# lighthouse-v01.net
KiCad netlist of a schematic drawn in EAGLE
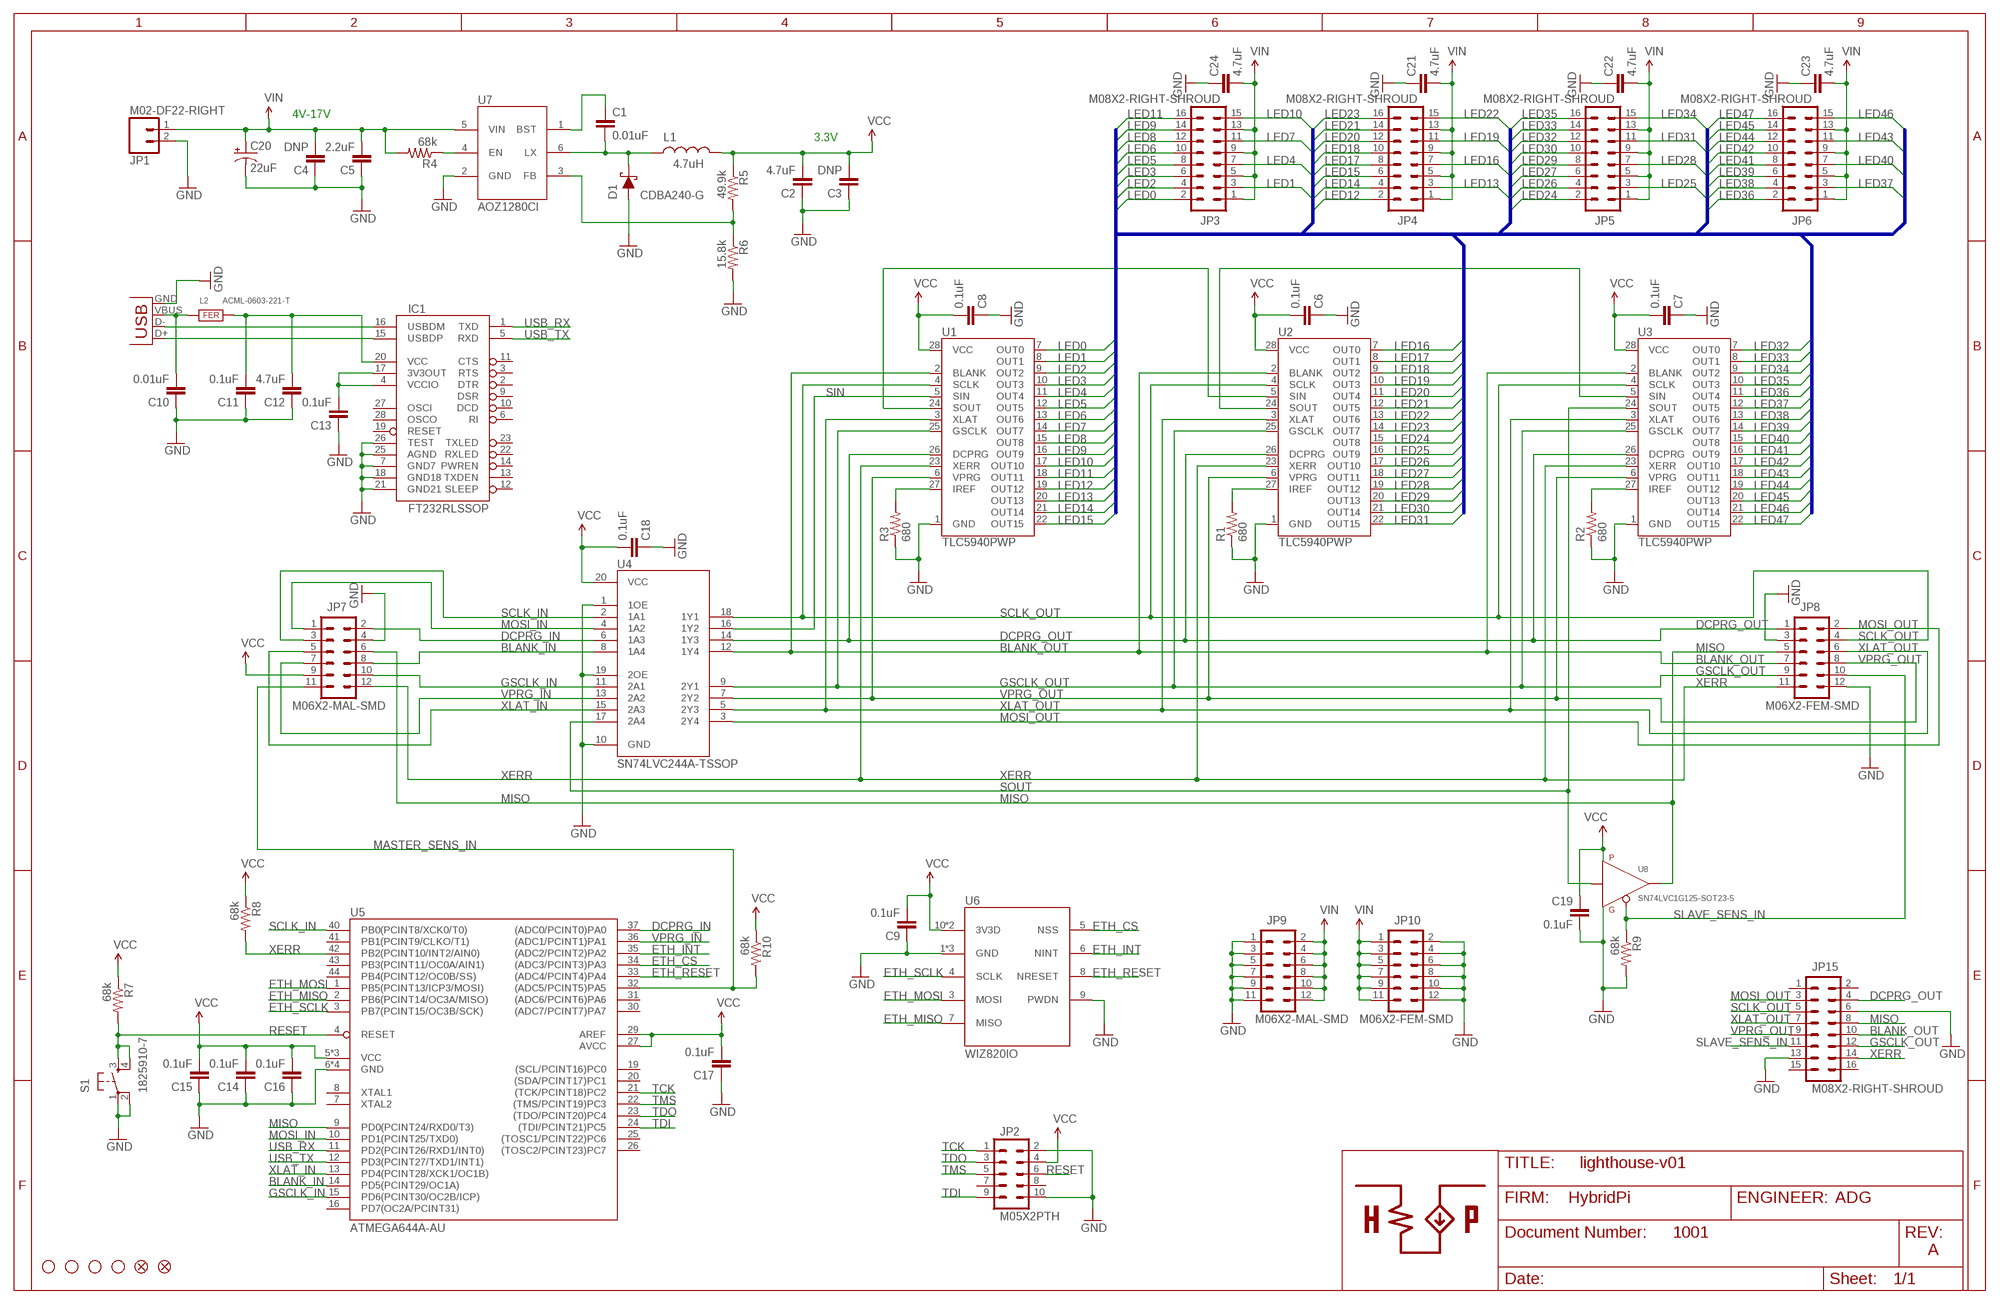
[diagram p0: schematic, sheet 1]

(export (version "E")
  (design (tool "Eeschema 10.0.6"))
  (components
    (comp (ref "C1")
      (value "0.01uF")
      (footprint "eagle-import:0603-CAP")
      (libsource (lib "eagle-import") (part "CAP0603-CAP"))
    )
    (comp (ref "C2")
      (value "4.7uF")
      (footprint "eagle-import:0805")
      (libsource (lib "eagle-import") (part "CAP0805"))
    )
    (comp (ref "C3")
      (value "DNP")
      (footprint "eagle-import:0805")
      (libsource (lib "eagle-import") (part "CAP0805"))
    )
    (comp (ref "C4")
      (value "DNP")
      (footprint "eagle-import:0805")
      (libsource (lib "eagle-import") (part "CAP0805"))
    )
    (comp (ref "C5")
      (value "2.2uF")
      (footprint "eagle-import:0805")
      (libsource (lib "eagle-import") (part "CAP0805"))
    )
    (comp (ref "C6")
      (value "0.1uF")
      (footprint "eagle-import:0603-CAP")
      (libsource (lib "eagle-import") (part "CAP0603-CAP"))
    )
    (comp (ref "C7")
      (value "0.1uF")
      (footprint "eagle-import:0603-CAP")
      (libsource (lib "eagle-import") (part "CAP0603-CAP"))
    )
    (comp (ref "C8")
      (value "0.1uF")
      (footprint "eagle-import:0603-CAP")
      (libsource (lib "eagle-import") (part "CAP0603-CAP"))
    )
    (comp (ref "C9")
      (value "0.1uF")
      (footprint "eagle-import:0603-CAP")
      (libsource (lib "eagle-import") (part "CAP0603-CAP"))
    )
    (comp (ref "C10")
      (value "0.01uF")
      (footprint "eagle-import:0603-CAP")
      (libsource (lib "eagle-import") (part "CAP0603-CAP"))
    )
    (comp (ref "C11")
      (value "0.1uF")
      (footprint "eagle-import:0603-CAP")
      (libsource (lib "eagle-import") (part "CAP0603-CAP"))
    )
    (comp (ref "C12")
      (value "4.7uF")
      (footprint "eagle-import:0805")
      (libsource (lib "eagle-import") (part "SparkFun-Passives_CAP0805"))
    )
    (comp (ref "C13")
      (value "0.1uF")
      (footprint "eagle-import:0603-CAP")
      (libsource (lib "eagle-import") (part "CAP0603-CAP"))
    )
    (comp (ref "C14")
      (value "0.1uF")
      (footprint "eagle-import:0603-CAP")
      (libsource (lib "eagle-import") (part "CAP0603-CAP"))
    )
    (comp (ref "C15")
      (value "0.1uF")
      (footprint "eagle-import:0603-CAP")
      (libsource (lib "eagle-import") (part "CAP0603-CAP"))
    )
    (comp (ref "C16")
      (value "0.1uF")
      (footprint "eagle-import:0603-CAP")
      (libsource (lib "eagle-import") (part "CAP0603-CAP"))
    )
    (comp (ref "C17")
      (value "0.1uF")
      (footprint "eagle-import:0603-CAP")
      (libsource (lib "eagle-import") (part "CAP0603-CAP"))
    )
    (comp (ref "C18")
      (value "0.1uF")
      (footprint "eagle-import:0603-CAP")
      (libsource (lib "eagle-import") (part "CAP0603-CAP"))
    )
    (comp (ref "C19")
      (value "0.1uF")
      (footprint "eagle-import:0603-CAP")
      (libsource (lib "eagle-import") (part "CAP0603-CAP"))
    )
    (comp (ref "C20")
      (value "22uF")
      (footprint "eagle-import:NIPPON_F80")
      (libsource (lib "eagle-import") (part "CAP_POLF80"))
    )
    (comp (ref "C21")
      (value "4.7uF")
      (footprint "eagle-import:1206")
      (libsource (lib "eagle-import") (part "SparkFun-Passives_CAP1206"))
    )
    (comp (ref "C22")
      (value "4.7uF")
      (footprint "eagle-import:1206")
      (libsource (lib "eagle-import") (part "SparkFun-Passives_CAP1206"))
    )
    (comp (ref "C23")
      (value "4.7uF")
      (footprint "eagle-import:1206")
      (libsource (lib "eagle-import") (part "SparkFun-Passives_CAP1206"))
    )
    (comp (ref "C24")
      (value "4.7uF")
      (footprint "eagle-import:1206")
      (libsource (lib "eagle-import") (part "SparkFun-Passives_CAP1206"))
    )
    (comp (ref "D1")
      (value "CDBA240-G")
      (footprint "eagle-import:DIODE-SMA")
      (libsource (lib "eagle-import") (part "DIODE-SCHOTTKY-SMA"))
    )
    (comp (ref "IC1")
      (value "FT232RLSSOP")
      (footprint "eagle-import:SSOP28DB")
      (libsource (lib "eagle-import") (part "FT232RLSSOP"))
    )
    (comp (ref "JP1")
      (value "M02-DF22-RIGHT")
      (footprint "eagle-import:M02-DF22-RIGHT")
      (libsource (lib "eagle-import") (part "M02-DF22-RIGHT"))
    )
    (comp (ref "JP2")
      (value "M05X2PTH")
      (footprint "eagle-import:AVR_ICSP")
      (libsource (lib "eagle-import") (part "M05X2PTH"))
    )
    (comp (ref "JP3")
      (value "M08X2-RIGHT-SHROUD")
      (footprint "eagle-import:2X8-RIGHT-SHROUD")
      (libsource (lib "eagle-import") (part "M08X2-RIGHT-SHROUD"))
    )
    (comp (ref "JP4")
      (value "M08X2-RIGHT-SHROUD")
      (footprint "eagle-import:2X8-RIGHT-SHROUD")
      (libsource (lib "eagle-import") (part "M08X2-RIGHT-SHROUD"))
    )
    (comp (ref "JP5")
      (value "M08X2-RIGHT-SHROUD")
      (footprint "eagle-import:2X8-RIGHT-SHROUD")
      (libsource (lib "eagle-import") (part "M08X2-RIGHT-SHROUD"))
    )
    (comp (ref "JP6")
      (value "M08X2-RIGHT-SHROUD")
      (footprint "eagle-import:2X8-RIGHT-SHROUD")
      (libsource (lib "eagle-import") (part "M08X2-RIGHT-SHROUD"))
    )
    (comp (ref "JP7")
      (value "M06X2-MAL-SMD")
      (footprint "eagle-import:2X6-SMD")
      (fields (field (name "EAGLEUP") "M06X2-MAL-SMD"))
      (libsource (lib "eagle-import") (part "M06X2-MAL-SMD"))
    )
    (comp (ref "JP8")
      (value "M06X2-FEM-SMD")
      (footprint "eagle-import:2X6-SMD")
      (libsource (lib "eagle-import") (part "M06X2-FEM-SMD"))
    )
    (comp (ref "JP9")
      (value "M06X2-MAL-SMD")
      (footprint "eagle-import:2X6-SMD")
      (fields (field (name "EAGLEUP") "M06X2-MAL-SMD"))
      (libsource (lib "eagle-import") (part "M06X2-MAL-SMD"))
    )
    (comp (ref "JP10")
      (value "M06X2-FEM-SMD")
      (footprint "eagle-import:2X6-SMD")
      (libsource (lib "eagle-import") (part "M06X2-FEM-SMD"))
    )
    (comp (ref "JP11")
      (value "STAND-OFF")
      (footprint "eagle-import:STAND-OFF")
      (libsource (lib "eagle-import") (part "STAND-OFF"))
    )
    (comp (ref "JP12")
      (value "STAND-OFF")
      (footprint "eagle-import:STAND-OFF")
      (libsource (lib "eagle-import") (part "STAND-OFF"))
    )
    (comp (ref "JP13")
      (value "STAND-OFF")
      (footprint "eagle-import:STAND-OFF")
      (libsource (lib "eagle-import") (part "STAND-OFF"))
    )
    (comp (ref "JP14")
      (value "STAND-OFF")
      (footprint "eagle-import:STAND-OFF")
      (libsource (lib "eagle-import") (part "STAND-OFF"))
    )
    (comp (ref "JP15")
      (value "M08X2-RIGHT-SHROUD")
      (footprint "eagle-import:2X8-RIGHT-SHROUD")
      (libsource (lib "eagle-import") (part "M08X2-RIGHT-SHROUD"))
    )
    (comp (ref "JP16")
      (value "FIDUCIAL1.5X3")
      (footprint "eagle-import:FIDUCIAL-1.5X3")
      (libsource (lib "eagle-import") (part "FIDUCIAL1.5X3"))
    )
    (comp (ref "JP17")
      (value "FIDUCIAL1.5X3")
      (footprint "eagle-import:FIDUCIAL-1.5X3")
      (libsource (lib "eagle-import") (part "FIDUCIAL1.5X3"))
    )
    (comp (ref "L1")
      (value "4.7uH")
      (footprint "eagle-import:SRN6045")
      (libsource (lib "eagle-import") (part "INDUCTOR-SRN6045"))
    )
    (comp (ref "L2")
      (value "ACML-0603-221-T")
      (footprint "eagle-import:0603")
      (libsource (lib "eagle-import") (part "FERRITE-BEAD-0603"))
    )
    (comp (ref "R1")
      (value "680")
      (footprint "eagle-import:0603-RES")
      (libsource (lib "eagle-import") (part "RESISTOR0603-RES"))
    )
    (comp (ref "R2")
      (value "680")
      (footprint "eagle-import:0603-RES")
      (libsource (lib "eagle-import") (part "RESISTOR0603-RES"))
    )
    (comp (ref "R3")
      (value "680")
      (footprint "eagle-import:0603-RES")
      (libsource (lib "eagle-import") (part "RESISTOR0603-RES"))
    )
    (comp (ref "R4")
      (value "68k")
      (footprint "eagle-import:0603-RES")
      (libsource (lib "eagle-import") (part "RESISTOR0603-RES"))
    )
    (comp (ref "R5")
      (value "49.9k")
      (footprint "eagle-import:0603-RES")
      (libsource (lib "eagle-import") (part "RESISTOR0603-RES"))
    )
    (comp (ref "R6")
      (value "15.8k")
      (footprint "eagle-import:0603-RES")
      (libsource (lib "eagle-import") (part "RESISTOR0603-RES"))
    )
    (comp (ref "R7")
      (value "68k")
      (footprint "eagle-import:0603-RES")
      (libsource (lib "eagle-import") (part "RESISTOR0603-RES"))
    )
    (comp (ref "R8")
      (value "68k")
      (footprint "eagle-import:0603-RES")
      (libsource (lib "eagle-import") (part "RESISTOR0603-RES"))
    )
    (comp (ref "R9")
      (value "68k")
      (footprint "eagle-import:0603-RES")
      (libsource (lib "eagle-import") (part "RESISTOR0603-RES"))
    )
    (comp (ref "R10")
      (value "68k")
      (footprint "eagle-import:0603-RES")
      (libsource (lib "eagle-import") (part "RESISTOR0603-RES"))
    )
    (comp (ref "S1")
      (value "1825910-7")
      (footprint "eagle-import:TACTILE-PTH")
      (libsource (lib "eagle-import") (part "TAC_SWITCHPTH"))
    )
    (comp (ref "U1")
      (value "TLC5940PWP")
      (footprint "eagle-import:TSSOP28-GROUNDPAD")
      (libsource (lib "eagle-import") (part "TLC5940PWP"))
    )
    (comp (ref "U2")
      (value "TLC5940PWP")
      (footprint "eagle-import:TSSOP28-GROUNDPAD")
      (libsource (lib "eagle-import") (part "TLC5940PWP"))
    )
    (comp (ref "U3")
      (value "TLC5940PWP")
      (footprint "eagle-import:TSSOP28-GROUNDPAD")
      (libsource (lib "eagle-import") (part "TLC5940PWP"))
    )
    (comp (ref "U4")
      (value "SN74LVC244A-TSSOP")
      (footprint "eagle-import:TSSOP-20")
      (libsource (lib "eagle-import") (part "SN74LVC244A-TSSOP"))
    )
    (comp (ref "U5")
      (value "ATMEGA644A-AU")
      (footprint "eagle-import:TQFP-44")
      (libsource (lib "eagle-import") (part "ATMEGA644A-AU"))
    )
    (comp (ref "U6")
      (value "WIZ820IO")
      (footprint "eagle-import:WIZ820IO")
      (libsource (lib "eagle-import") (part "WIZ820IO"))
    )
    (comp (ref "U7")
      (value "AOZ1280CI")
      (footprint "eagle-import:SOT23-6")
      (libsource (lib "eagle-import") (part "AOZ1280CI"))
    )
    (comp (ref "U8")
      (value "SN74LVC1G125-SOT23-5")
      (footprint "eagle-import:SOT23-5")
      (libsource (lib "eagle-import") (part "SN74LVC1G125-SOT23-5"))
    )
    (comp (ref "X1")
      (value "USBSMD")
      (footprint "eagle-import:USB-MINIB")
      (libsource (lib "eagle-import") (part "USBSMD"))
    )
  )
  (nets
    (net (code "1") (name "/BLANK_IN") (class "Default")
      (node (ref "JP7") (pin "8") (pinfunction "8_8") (pintype "passive"))
      (node (ref "U4") (pin "8") (pinfunction "1A4_8") (pintype "bidirectional"))
      (node (ref "U5") (pin "14") (pinfunction "PD5(PCINT29/OC1A)_14") (pintype "bidirectional"))
    )
    (net (code "2") (name "/BLANK_OUT") (class "Default")
      (node (ref "JP15") (pin "10") (pinfunction "10_10") (pintype "passive"))
      (node (ref "JP8") (pin "7") (pinfunction "7_7") (pintype "passive"))
      (node (ref "U1") (pin "2") (pinfunction "BLANK_2") (pintype "bidirectional"))
      (node (ref "U2") (pin "2") (pinfunction "BLANK_2") (pintype "bidirectional"))
      (node (ref "U3") (pin "2") (pinfunction "BLANK_2") (pintype "bidirectional"))
      (node (ref "U4") (pin "12") (pinfunction "1Y4_12") (pintype "bidirectional"))
    )
    (net (code "3") (name "/DCPRG_IN") (class "Default")
      (node (ref "JP7") (pin "2") (pinfunction "2_2") (pintype "passive"))
      (node (ref "U4") (pin "6") (pinfunction "1A3_6") (pintype "bidirectional"))
      (node (ref "U5") (pin "37") (pinfunction "(ADC0/PCINT0)PA0_37") (pintype "bidirectional"))
    )
    (net (code "4") (name "/DCPRG_OUT") (class "Default")
      (node (ref "JP15") (pin "4") (pinfunction "4_4") (pintype "passive"))
      (node (ref "JP8") (pin "1") (pinfunction "1_1") (pintype "passive"))
      (node (ref "U1") (pin "26") (pinfunction "DCPRG_26") (pintype "bidirectional"))
      (node (ref "U2") (pin "26") (pinfunction "DCPRG_26") (pintype "bidirectional"))
      (node (ref "U3") (pin "26") (pinfunction "DCPRG_26") (pintype "bidirectional"))
      (node (ref "U4") (pin "14") (pinfunction "1Y3_14") (pintype "bidirectional"))
    )
    (net (code "5") (name "/ETH_CS") (class "Default")
      (node (ref "U5") (pin "34") (pinfunction "(ADC3/PCINT3)PA3_34") (pintype "bidirectional"))
      (node (ref "U6") (pin "5") (pinfunction "NSS_5") (pintype "bidirectional"))
    )
    (net (code "6") (name "/ETH_INT") (class "Default")
      (node (ref "U5") (pin "35") (pinfunction "(ADC2/PCINT2)PA2_35") (pintype "bidirectional"))
      (node (ref "U6") (pin "6") (pinfunction "NINT_6") (pintype "bidirectional"))
    )
    (net (code "7") (name "/ETH_MISO") (class "Default")
      (node (ref "U5") (pin "2") (pinfunction "PB6(PCINT14/OC3A/MISO)_2") (pintype "bidirectional"))
      (node (ref "U6") (pin "7") (pinfunction "MISO_7") (pintype "bidirectional"))
    )
    (net (code "8") (name "/ETH_MOSI") (class "Default")
      (node (ref "U5") (pin "1") (pinfunction "PB5(PCINT13/ICP3/MOSI)_1") (pintype "bidirectional"))
      (node (ref "U6") (pin "3") (pinfunction "MOSI_3") (pintype "bidirectional"))
    )
    (net (code "9") (name "/ETH_RESET") (class "Default")
      (node (ref "U5") (pin "33") (pinfunction "(ADC4/PCINT4)PA4_33") (pintype "bidirectional"))
      (node (ref "U6") (pin "8") (pinfunction "NRESET_8") (pintype "bidirectional"))
    )
    (net (code "10") (name "/ETH_SCLK") (class "Default")
      (node (ref "U5") (pin "3") (pinfunction "PB7(PCINT15/OC3B/SCK)_3") (pintype "bidirectional"))
      (node (ref "U6") (pin "4") (pinfunction "SCLK_4") (pintype "bidirectional"))
    )
    (net (code "11") (name "/GSCLK_IN") (class "Default")
      (node (ref "JP7") (pin "10") (pinfunction "10_10") (pintype "passive"))
      (node (ref "U4") (pin "11") (pinfunction "2A1_11") (pintype "bidirectional"))
      (node (ref "U5") (pin "15") (pinfunction "PD6(PCINT30/OC2B/ICP)_15") (pintype "bidirectional"))
    )
    (net (code "12") (name "/GSCLK_OUT") (class "Default")
      (node (ref "JP15") (pin "12") (pinfunction "12_12") (pintype "passive"))
      (node (ref "JP8") (pin "9") (pinfunction "9_9") (pintype "passive"))
      (node (ref "U1") (pin "25") (pinfunction "GSCLK_25") (pintype "bidirectional"))
      (node (ref "U2") (pin "25") (pinfunction "GSCLK_25") (pintype "bidirectional"))
      (node (ref "U3") (pin "25") (pinfunction "GSCLK_25") (pintype "bidirectional"))
      (node (ref "U4") (pin "9") (pinfunction "2Y1_9") (pintype "bidirectional"))
    )
    (net (code "13") (name "/LED0") (class "Default")
      (node (ref "JP3") (pin "2") (pinfunction "2_2") (pintype "passive"))
      (node (ref "U1") (pin "7") (pinfunction "OUT0_7") (pintype "bidirectional"))
    )
    (net (code "14") (name "/LED1") (class "Default")
      (node (ref "JP3") (pin "3") (pinfunction "3_3") (pintype "passive"))
      (node (ref "U1") (pin "8") (pinfunction "OUT1_8") (pintype "bidirectional"))
    )
    (net (code "15") (name "/LED2") (class "Default")
      (node (ref "JP3") (pin "4") (pinfunction "4_4") (pintype "passive"))
      (node (ref "U1") (pin "9") (pinfunction "OUT2_9") (pintype "bidirectional"))
    )
    (net (code "16") (name "/LED3") (class "Default")
      (node (ref "JP3") (pin "6") (pinfunction "6_6") (pintype "passive"))
      (node (ref "U1") (pin "10") (pinfunction "OUT3_10") (pintype "bidirectional"))
    )
    (net (code "17") (name "/LED4") (class "Default")
      (node (ref "JP3") (pin "7") (pinfunction "7_7") (pintype "passive"))
      (node (ref "U1") (pin "11") (pinfunction "OUT4_11") (pintype "bidirectional"))
    )
    (net (code "18") (name "/LED5") (class "Default")
      (node (ref "JP3") (pin "8") (pinfunction "8_8") (pintype "passive"))
      (node (ref "U1") (pin "12") (pinfunction "OUT5_12") (pintype "bidirectional"))
    )
    (net (code "19") (name "/LED6") (class "Default")
      (node (ref "JP3") (pin "10") (pinfunction "10_10") (pintype "passive"))
      (node (ref "U1") (pin "13") (pinfunction "OUT6_13") (pintype "bidirectional"))
    )
    (net (code "20") (name "/LED7") (class "Default")
      (node (ref "JP3") (pin "11") (pinfunction "11_11") (pintype "passive"))
      (node (ref "U1") (pin "14") (pinfunction "OUT7_14") (pintype "bidirectional"))
    )
    (net (code "21") (name "/LED8") (class "Default")
      (node (ref "JP3") (pin "12") (pinfunction "12_12") (pintype "passive"))
      (node (ref "U1") (pin "15") (pinfunction "OUT8_15") (pintype "bidirectional"))
    )
    (net (code "22") (name "/LED9") (class "Default")
      (node (ref "JP3") (pin "14") (pinfunction "14_14") (pintype "passive"))
      (node (ref "U1") (pin "16") (pinfunction "OUT9_16") (pintype "bidirectional"))
    )
    (net (code "23") (name "/LED10") (class "Default")
      (node (ref "JP3") (pin "15") (pinfunction "15_15") (pintype "passive"))
      (node (ref "U1") (pin "17") (pinfunction "OUT10_17") (pintype "bidirectional"))
    )
    (net (code "24") (name "/LED11") (class "Default")
      (node (ref "JP3") (pin "16") (pinfunction "16_16") (pintype "passive"))
      (node (ref "U1") (pin "18") (pinfunction "OUT11_18") (pintype "bidirectional"))
    )
    (net (code "25") (name "/LED12") (class "Default")
      (node (ref "JP4") (pin "2") (pinfunction "2_2") (pintype "passive"))
      (node (ref "U1") (pin "19") (pinfunction "OUT12_19") (pintype "bidirectional"))
    )
    (net (code "26") (name "/LED13") (class "Default")
      (node (ref "JP4") (pin "3") (pinfunction "3_3") (pintype "passive"))
      (node (ref "U1") (pin "20") (pinfunction "OUT13_20") (pintype "bidirectional"))
    )
    (net (code "27") (name "/LED14") (class "Default")
      (node (ref "JP4") (pin "4") (pinfunction "4_4") (pintype "passive"))
      (node (ref "U1") (pin "21") (pinfunction "OUT14_21") (pintype "bidirectional"))
    )
    (net (code "28") (name "/LED15") (class "Default")
      (node (ref "JP4") (pin "6") (pinfunction "6_6") (pintype "passive"))
      (node (ref "U1") (pin "22") (pinfunction "OUT15_22") (pintype "bidirectional"))
    )
    (net (code "29") (name "/LED16") (class "Default")
      (node (ref "JP4") (pin "7") (pinfunction "7_7") (pintype "passive"))
      (node (ref "U2") (pin "7") (pinfunction "OUT0_7") (pintype "bidirectional"))
    )
    (net (code "30") (name "/LED17") (class "Default")
      (node (ref "JP4") (pin "8") (pinfunction "8_8") (pintype "passive"))
      (node (ref "U2") (pin "8") (pinfunction "OUT1_8") (pintype "bidirectional"))
    )
    (net (code "31") (name "/LED18") (class "Default")
      (node (ref "JP4") (pin "10") (pinfunction "10_10") (pintype "passive"))
      (node (ref "U2") (pin "9") (pinfunction "OUT2_9") (pintype "bidirectional"))
    )
    (net (code "32") (name "/LED19") (class "Default")
      (node (ref "JP4") (pin "11") (pinfunction "11_11") (pintype "passive"))
      (node (ref "U2") (pin "10") (pinfunction "OUT3_10") (pintype "bidirectional"))
    )
    (net (code "33") (name "/LED20") (class "Default")
      (node (ref "JP4") (pin "12") (pinfunction "12_12") (pintype "passive"))
      (node (ref "U2") (pin "11") (pinfunction "OUT4_11") (pintype "bidirectional"))
    )
    (net (code "34") (name "/LED21") (class "Default")
      (node (ref "JP4") (pin "14") (pinfunction "14_14") (pintype "passive"))
      (node (ref "U2") (pin "12") (pinfunction "OUT5_12") (pintype "bidirectional"))
    )
    (net (code "35") (name "/LED22") (class "Default")
      (node (ref "JP4") (pin "15") (pinfunction "15_15") (pintype "passive"))
      (node (ref "U2") (pin "13") (pinfunction "OUT6_13") (pintype "bidirectional"))
    )
    (net (code "36") (name "/LED23") (class "Default")
      (node (ref "JP4") (pin "16") (pinfunction "16_16") (pintype "passive"))
      (node (ref "U2") (pin "14") (pinfunction "OUT7_14") (pintype "bidirectional"))
    )
    (net (code "37") (name "/LED24") (class "Default")
      (node (ref "JP5") (pin "2") (pinfunction "2_2") (pintype "passive"))
      (node (ref "U2") (pin "15") (pinfunction "OUT8_15") (pintype "bidirectional"))
    )
    (net (code "38") (name "/LED25") (class "Default")
      (node (ref "JP5") (pin "3") (pinfunction "3_3") (pintype "passive"))
      (node (ref "U2") (pin "16") (pinfunction "OUT9_16") (pintype "bidirectional"))
    )
    (net (code "39") (name "/LED26") (class "Default")
      (node (ref "JP5") (pin "4") (pinfunction "4_4") (pintype "passive"))
      (node (ref "U2") (pin "17") (pinfunction "OUT10_17") (pintype "bidirectional"))
    )
    (net (code "40") (name "/LED27") (class "Default")
      (node (ref "JP5") (pin "6") (pinfunction "6_6") (pintype "passive"))
      (node (ref "U2") (pin "18") (pinfunction "OUT11_18") (pintype "bidirectional"))
    )
    (net (code "41") (name "/LED28") (class "Default")
      (node (ref "JP5") (pin "7") (pinfunction "7_7") (pintype "passive"))
      (node (ref "U2") (pin "19") (pinfunction "OUT12_19") (pintype "bidirectional"))
    )
    (net (code "42") (name "/LED29") (class "Default")
      (node (ref "JP5") (pin "8") (pinfunction "8_8") (pintype "passive"))
      (node (ref "U2") (pin "20") (pinfunction "OUT13_20") (pintype "bidirectional"))
    )
    (net (code "43") (name "/LED30") (class "Default")
      (node (ref "JP5") (pin "10") (pinfunction "10_10") (pintype "passive"))
      (node (ref "U2") (pin "21") (pinfunction "OUT14_21") (pintype "bidirectional"))
    )
    (net (code "44") (name "/LED31") (class "Default")
      (node (ref "JP5") (pin "11") (pinfunction "11_11") (pintype "passive"))
      (node (ref "U2") (pin "22") (pinfunction "OUT15_22") (pintype "bidirectional"))
    )
    (net (code "45") (name "/LED32") (class "Default")
      (node (ref "JP5") (pin "12") (pinfunction "12_12") (pintype "passive"))
      (node (ref "U3") (pin "7") (pinfunction "OUT0_7") (pintype "bidirectional"))
    )
    (net (code "46") (name "/LED33") (class "Default")
      (node (ref "JP5") (pin "14") (pinfunction "14_14") (pintype "passive"))
      (node (ref "U3") (pin "8") (pinfunction "OUT1_8") (pintype "bidirectional"))
    )
    (net (code "47") (name "/LED34") (class "Default")
      (node (ref "JP5") (pin "15") (pinfunction "15_15") (pintype "passive"))
      (node (ref "U3") (pin "9") (pinfunction "OUT2_9") (pintype "bidirectional"))
    )
    (net (code "48") (name "/LED35") (class "Default")
      (node (ref "JP5") (pin "16") (pinfunction "16_16") (pintype "passive"))
      (node (ref "U3") (pin "10") (pinfunction "OUT3_10") (pintype "bidirectional"))
    )
    (net (code "49") (name "/LED36") (class "Default")
      (node (ref "JP6") (pin "2") (pinfunction "2_2") (pintype "passive"))
      (node (ref "U3") (pin "11") (pinfunction "OUT4_11") (pintype "bidirectional"))
    )
    (net (code "50") (name "/LED37") (class "Default")
      (node (ref "JP6") (pin "3") (pinfunction "3_3") (pintype "passive"))
      (node (ref "U3") (pin "12") (pinfunction "OUT5_12") (pintype "bidirectional"))
    )
    (net (code "51") (name "/LED38") (class "Default")
      (node (ref "JP6") (pin "4") (pinfunction "4_4") (pintype "passive"))
      (node (ref "U3") (pin "13") (pinfunction "OUT6_13") (pintype "bidirectional"))
    )
    (net (code "52") (name "/LED39") (class "Default")
      (node (ref "JP6") (pin "6") (pinfunction "6_6") (pintype "passive"))
      (node (ref "U3") (pin "14") (pinfunction "OUT7_14") (pintype "bidirectional"))
    )
    (net (code "53") (name "/LED40") (class "Default")
      (node (ref "JP6") (pin "7") (pinfunction "7_7") (pintype "passive"))
      (node (ref "U3") (pin "15") (pinfunction "OUT8_15") (pintype "bidirectional"))
    )
    (net (code "54") (name "/LED41") (class "Default")
      (node (ref "JP6") (pin "8") (pinfunction "8_8") (pintype "passive"))
      (node (ref "U3") (pin "16") (pinfunction "OUT9_16") (pintype "bidirectional"))
    )
    (net (code "55") (name "/LED42") (class "Default")
      (node (ref "JP6") (pin "10") (pinfunction "10_10") (pintype "passive"))
      (node (ref "U3") (pin "17") (pinfunction "OUT10_17") (pintype "bidirectional"))
    )
    (net (code "56") (name "/LED43") (class "Default")
      (node (ref "JP6") (pin "11") (pinfunction "11_11") (pintype "passive"))
      (node (ref "U3") (pin "18") (pinfunction "OUT11_18") (pintype "bidirectional"))
    )
    (net (code "57") (name "/LED44") (class "Default")
      (node (ref "JP6") (pin "12") (pinfunction "12_12") (pintype "passive"))
      (node (ref "U3") (pin "19") (pinfunction "OUT12_19") (pintype "bidirectional"))
    )
    (net (code "58") (name "/LED45") (class "Default")
      (node (ref "JP6") (pin "14") (pinfunction "14_14") (pintype "passive"))
      (node (ref "U3") (pin "20") (pinfunction "OUT13_20") (pintype "bidirectional"))
    )
    (net (code "59") (name "/LED46") (class "Default")
      (node (ref "JP6") (pin "15") (pinfunction "15_15") (pintype "passive"))
      (node (ref "U3") (pin "21") (pinfunction "OUT14_21") (pintype "bidirectional"))
    )
    (net (code "60") (name "/LED47") (class "Default")
      (node (ref "JP6") (pin "16") (pinfunction "16_16") (pintype "passive"))
      (node (ref "U3") (pin "22") (pinfunction "OUT15_22") (pintype "bidirectional"))
    )
    (net (code "61") (name "/MASTER_SENS_IN") (class "Default")
      (node (ref "JP7") (pin "11") (pinfunction "11_11") (pintype "passive"))
      (node (ref "R10") (pin "2") (pinfunction "2_2") (pintype "passive"))
      (node (ref "U5") (pin "32") (pinfunction "(ADC5/PCINT5)PA5_32") (pintype "bidirectional"))
    )
    (net (code "62") (name "/MISO") (class "Default")
      (node (ref "JP15") (pin "8") (pinfunction "8_8") (pintype "passive"))
      (node (ref "JP7") (pin "6") (pinfunction "6_6") (pintype "passive"))
      (node (ref "JP8") (pin "5") (pinfunction "5_5") (pintype "passive"))
      (node (ref "U5") (pin "9") (pinfunction "PD0(PCINT24/RXD0/T3)_9") (pintype "bidirectional"))
      (node (ref "U8") (pin "4") (pinfunction "Y_4") (pintype "bidirectional"))
    )
    (net (code "63") (name "/MOSI_IN") (class "Default")
      (node (ref "JP7") (pin "1") (pinfunction "1_1") (pintype "passive"))
      (node (ref "U4") (pin "4") (pinfunction "1A2_4") (pintype "bidirectional"))
      (node (ref "U5") (pin "10") (pinfunction "PD1(PCINT25/TXD0)_10") (pintype "bidirectional"))
    )
    (net (code "64") (name "/MOSI_OUT") (class "Default")
      (node (ref "JP15") (pin "3") (pinfunction "3_3") (pintype "passive"))
      (node (ref "JP8") (pin "2") (pinfunction "2_2") (pintype "passive"))
      (node (ref "U4") (pin "3") (pinfunction "2Y4_3") (pintype "bidirectional"))
    )
    (net (code "65") (name "/RESET") (class "Default")
      (node (ref "JP2") (pin "6") (pinfunction "6_6") (pintype "passive"))
      (node (ref "R7") (pin "2") (pinfunction "2_2") (pintype "passive"))
      (node (ref "S1") (pin "3") (pinfunction "3_3") (pintype "passive"))
      (node (ref "S1") (pin "4") (pinfunction "4_4") (pintype "passive"))
      (node (ref "U5") (pin "4") (pinfunction "RESET_4") (pintype "input"))
    )
    (net (code "66") (name "/SCLK_IN") (class "Default")
      (node (ref "JP7") (pin "3") (pinfunction "3_3") (pintype "passive"))
      (node (ref "U4") (pin "2") (pinfunction "1A1_2") (pintype "bidirectional"))
      (node (ref "U5") (pin "40") (pinfunction "PB0(PCINT8/XCK0/T0)_40") (pintype "bidirectional"))
    )
    (net (code "67") (name "/SCLK_OUT") (class "Default")
      (node (ref "JP15") (pin "5") (pinfunction "5_5") (pintype "passive"))
      (node (ref "JP8") (pin "4") (pinfunction "4_4") (pintype "passive"))
      (node (ref "U1") (pin "4") (pinfunction "SCLK_4") (pintype "bidirectional"))
      (node (ref "U2") (pin "4") (pinfunction "SCLK_4") (pintype "bidirectional"))
      (node (ref "U3") (pin "4") (pinfunction "SCLK_4") (pintype "bidirectional"))
      (node (ref "U4") (pin "18") (pinfunction "1Y1_18") (pintype "bidirectional"))
    )
    (net (code "68") (name "/SIN") (class "Default")
      (node (ref "U1") (pin "5") (pinfunction "SIN_5") (pintype "bidirectional"))
      (node (ref "U4") (pin "16") (pinfunction "1Y2_16") (pintype "bidirectional"))
    )
    (net (code "69") (name "/SLAVE_SENS_IN") (class "Default")
      (node (ref "JP15") (pin "11") (pinfunction "11_11") (pintype "passive"))
      (node (ref "JP8") (pin "10") (pinfunction "10_10") (pintype "passive"))
      (node (ref "R9") (pin "1") (pinfunction "1_1") (pintype "passive"))
      (node (ref "U8") (pin "1") (pinfunction "OE_1") (pintype "input"))
    )
    (net (code "70") (name "/SOUT") (class "Default")
      (node (ref "U3") (pin "24") (pinfunction "SOUT_24") (pintype "bidirectional"))
      (node (ref "U4") (pin "17") (pinfunction "2A4_17") (pintype "bidirectional"))
      (node (ref "U8") (pin "2") (pinfunction "A_2") (pintype "input"))
    )
    (net (code "71") (name "/TCK") (class "Default")
      (node (ref "JP2") (pin "1") (pinfunction "1_1") (pintype "passive"))
      (node (ref "U5") (pin "21") (pinfunction "(TCK/PCINT18)PC2_21") (pintype "bidirectional"))
    )
    (net (code "72") (name "/TDI") (class "Default")
      (node (ref "JP2") (pin "9") (pinfunction "9_9") (pintype "passive"))
      (node (ref "U5") (pin "24") (pinfunction "(TDI/PCINT21)PC5_24") (pintype "bidirectional"))
    )
    (net (code "73") (name "/TDO") (class "Default")
      (node (ref "JP2") (pin "3") (pinfunction "3_3") (pintype "passive"))
      (node (ref "U5") (pin "23") (pinfunction "(TDO/PCINT20)PC4_23") (pintype "bidirectional"))
    )
    (net (code "74") (name "/TMS") (class "Default")
      (node (ref "JP2") (pin "5") (pinfunction "5_5") (pintype "passive"))
      (node (ref "U5") (pin "22") (pinfunction "(TMS/PCINT19)PC3_22") (pintype "bidirectional"))
    )
    (net (code "75") (name "/USB_RX") (class "Default")
      (node (ref "IC1") (pin "1") (pinfunction "TXD_1") (pintype "output"))
      (node (ref "U5") (pin "11") (pinfunction "PD2(PCINT26/RXD1/INT0)_11") (pintype "bidirectional"))
    )
    (net (code "76") (name "/USB_TX") (class "Default")
      (node (ref "IC1") (pin "5") (pinfunction "RXD_5") (pintype "input"))
      (node (ref "U5") (pin "12") (pinfunction "PD3(PCINT27/TXD1/INT1)_12") (pintype "bidirectional"))
    )
    (net (code "77") (name "/VPRG_IN") (class "Default")
      (node (ref "JP7") (pin "7") (pinfunction "7_7") (pintype "passive"))
      (node (ref "U4") (pin "13") (pinfunction "2A2_13") (pintype "bidirectional"))
      (node (ref "U5") (pin "36") (pinfunction "(ADC1/PCINT1)PA1_36") (pintype "bidirectional"))
    )
    (net (code "78") (name "/VPRG_OUT") (class "Default")
      (node (ref "JP15") (pin "9") (pinfunction "9_9") (pintype "passive"))
      (node (ref "JP8") (pin "8") (pinfunction "8_8") (pintype "passive"))
      (node (ref "U1") (pin "6") (pinfunction "VPRG_6") (pintype "bidirectional"))
      (node (ref "U2") (pin "6") (pinfunction "VPRG_6") (pintype "bidirectional"))
      (node (ref "U3") (pin "6") (pinfunction "VPRG_6") (pintype "bidirectional"))
      (node (ref "U4") (pin "7") (pinfunction "2Y2_7") (pintype "bidirectional"))
    )
    (net (code "79") (name "/XERR") (class "Default")
      (node (ref "JP15") (pin "14") (pinfunction "14_14") (pintype "passive"))
      (node (ref "JP7") (pin "12") (pinfunction "12_12") (pintype "passive"))
      (node (ref "JP8") (pin "11") (pinfunction "11_11") (pintype "passive"))
      (node (ref "R8") (pin "2") (pinfunction "2_2") (pintype "passive"))
      (node (ref "U1") (pin "23") (pinfunction "XERR_23") (pintype "bidirectional"))
      (node (ref "U2") (pin "23") (pinfunction "XERR_23") (pintype "bidirectional"))
      (node (ref "U3") (pin "23") (pinfunction "XERR_23") (pintype "bidirectional"))
      (node (ref "U5") (pin "42") (pinfunction "PB2(PCINT10/INT2/AIN0)_42") (pintype "bidirectional"))
    )
    (net (code "80") (name "/XLAT_IN") (class "Default")
      (node (ref "JP7") (pin "5") (pinfunction "5_5") (pintype "passive"))
      (node (ref "U4") (pin "15") (pinfunction "2A3_15") (pintype "bidirectional"))
      (node (ref "U5") (pin "13") (pinfunction "PD4(PCINT28/XCK1/OC1B)_13") (pintype "bidirectional"))
    )
    (net (code "81") (name "/XLAT_OUT") (class "Default")
      (node (ref "JP15") (pin "7") (pinfunction "7_7") (pintype "passive"))
      (node (ref "JP8") (pin "6") (pinfunction "6_6") (pintype "passive"))
      (node (ref "U1") (pin "3") (pinfunction "XLAT_3") (pintype "bidirectional"))
      (node (ref "U2") (pin "3") (pinfunction "XLAT_3") (pintype "bidirectional"))
      (node (ref "U3") (pin "3") (pinfunction "XLAT_3") (pintype "bidirectional"))
      (node (ref "U4") (pin "5") (pinfunction "2Y3_5") (pintype "bidirectional"))
    )
    (net (code "82") (name "GND") (class "Default")
      (node (ref "C10") (pin "1") (pinfunction "1_1") (pintype "passive"))
      (node (ref "C11") (pin "1") (pinfunction "1_1") (pintype "passive"))
      (node (ref "C12") (pin "1") (pinfunction "1_1") (pintype "passive"))
      (node (ref "C13") (pin "1") (pinfunction "1_1") (pintype "passive"))
      (node (ref "C14") (pin "1") (pinfunction "1_1") (pintype "passive"))
      (node (ref "C15") (pin "1") (pinfunction "1_1") (pintype "passive"))
      (node (ref "C16") (pin "1") (pinfunction "1_1") (pintype "passive"))
      (node (ref "C17") (pin "1") (pinfunction "1_1") (pintype "passive"))
      (node (ref "C18") (pin "1") (pinfunction "1_1") (pintype "passive"))
      (node (ref "C19") (pin "2") (pinfunction "2_2") (pintype "passive"))
      (node (ref "C2") (pin "1") (pinfunction "1_1") (pintype "passive"))
      (node (ref "C20") (pin "-") (pinfunction "-_-") (pintype "passive"))
      (node (ref "C21") (pin "1") (pinfunction "1_1") (pintype "passive"))
      (node (ref "C22") (pin "1") (pinfunction "1_1") (pintype "passive"))
      (node (ref "C23") (pin "1") (pinfunction "1_1") (pintype "passive"))
      (node (ref "C24") (pin "1") (pinfunction "1_1") (pintype "passive"))
      (node (ref "C3") (pin "1") (pinfunction "1_1") (pintype "passive"))
      (node (ref "C4") (pin "1") (pinfunction "1_1") (pintype "passive"))
      (node (ref "C5") (pin "1") (pinfunction "1_1") (pintype "passive"))
      (node (ref "C6") (pin "1") (pinfunction "1_1") (pintype "passive"))
      (node (ref "C7") (pin "1") (pinfunction "1_1") (pintype "passive"))
      (node (ref "C8") (pin "1") (pinfunction "1_1") (pintype "passive"))
      (node (ref "C9") (pin "1") (pinfunction "1_1") (pintype "passive"))
      (node (ref "D1") (pin "A") (pinfunction "A_A") (pintype "bidirectional"))
      (node (ref "IC1") (pin "18") (pinfunction "GND18_18") (pintype "power_in"))
      (node (ref "IC1") (pin "21") (pinfunction "GND21_21") (pintype "power_in"))
      (node (ref "IC1") (pin "25") (pinfunction "AGND_25") (pintype "power_in"))
      (node (ref "IC1") (pin "26") (pinfunction "TEST_26") (pintype "input"))
      (node (ref "IC1") (pin "7") (pinfunction "GND7_7") (pintype "power_in"))
      (node (ref "JP1") (pin "2") (pinfunction "2_2") (pintype "passive"))
      (node (ref "JP10") (pin "10") (pinfunction "10_10") (pintype "passive"))
      (node (ref "JP10") (pin "12") (pinfunction "12_12") (pintype "passive"))
      (node (ref "JP10") (pin "2") (pinfunction "2_2") (pintype "passive"))
      (node (ref "JP10") (pin "4") (pinfunction "4_4") (pintype "passive"))
      (node (ref "JP10") (pin "6") (pinfunction "6_6") (pintype "passive"))
      (node (ref "JP10") (pin "8") (pinfunction "8_8") (pintype "passive"))
      (node (ref "JP15") (pin "13") (pinfunction "13_13") (pintype "passive"))
      (node (ref "JP15") (pin "6") (pinfunction "6_6") (pintype "passive"))
      (node (ref "JP2") (pin "10") (pinfunction "10_10") (pintype "passive"))
      (node (ref "JP2") (pin "2") (pinfunction "2_2") (pintype "passive"))
      (node (ref "JP7") (pin "4") (pinfunction "4_4") (pintype "passive"))
      (node (ref "JP8") (pin "12") (pinfunction "12_12") (pintype "passive"))
      (node (ref "JP8") (pin "3") (pinfunction "3_3") (pintype "passive"))
      (node (ref "JP9") (pin "1") (pinfunction "1_1") (pintype "passive"))
      (node (ref "JP9") (pin "11") (pinfunction "11_11") (pintype "passive"))
      (node (ref "JP9") (pin "3") (pinfunction "3_3") (pintype "passive"))
      (node (ref "JP9") (pin "5") (pinfunction "5_5") (pintype "passive"))
      (node (ref "JP9") (pin "7") (pinfunction "7_7") (pintype "passive"))
      (node (ref "JP9") (pin "9") (pinfunction "9_9") (pintype "passive"))
      (node (ref "R1") (pin "1") (pinfunction "1_1") (pintype "passive"))
      (node (ref "R2") (pin "1") (pinfunction "1_1") (pintype "passive"))
      (node (ref "R3") (pin "1") (pinfunction "1_1") (pintype "passive"))
      (node (ref "R6") (pin "2") (pinfunction "2_2") (pintype "passive"))
      (node (ref "R9") (pin "2") (pinfunction "2_2") (pintype "passive"))
      (node (ref "S1") (pin "1") (pinfunction "1_1") (pintype "passive"))
      (node (ref "S1") (pin "2") (pinfunction "2_2") (pintype "passive"))
      (node (ref "U1") (pin "1") (pinfunction "GND_1") (pintype "bidirectional"))
      (node (ref "U2") (pin "1") (pinfunction "GND_1") (pintype "bidirectional"))
      (node (ref "U3") (pin "1") (pinfunction "GND_1") (pintype "bidirectional"))
      (node (ref "U4") (pin "1") (pinfunction "1OE_1") (pintype "bidirectional"))
      (node (ref "U4") (pin "10") (pinfunction "GND_10") (pintype "bidirectional"))
      (node (ref "U4") (pin "19") (pinfunction "2OE_19") (pintype "bidirectional"))
      (node (ref "U5") (pin "18") (pinfunction "GND_18") (pintype "power_in"))
      (node (ref "U5") (pin "28") (pinfunction "GND_28") (pintype "power_in"))
      (node (ref "U5") (pin "39") (pinfunction "GND_39") (pintype "power_in"))
      (node (ref "U5") (pin "6") (pinfunction "GND_6") (pintype "power_in"))
      (node (ref "U6") (pin "1") (pinfunction "GND_1") (pintype "bidirectional"))
      (node (ref "U6") (pin "12") (pinfunction "GND_12") (pintype "bidirectional"))
      (node (ref "U6") (pin "2") (pinfunction "GND_2") (pintype "bidirectional"))
      (node (ref "U6") (pin "9") (pinfunction "PWDN_9") (pintype "bidirectional"))
      (node (ref "U7") (pin "2") (pinfunction "GND_2") (pintype "bidirectional"))
      (node (ref "U8") (pin "3") (pinfunction "GND_3") (pintype "power_in"))
      (node (ref "X1") (pin "GND") (pinfunction "GND_GND") (pintype "bidirectional"))
    )
    (net (code "83") (name "Net-(C10-Pad2)") (class "Default")
      (node (ref "C10") (pin "2") (pinfunction "2_2") (pintype "passive"))
      (node (ref "L2") (pin "1") (pinfunction "1_1") (pintype "bidirectional"))
      (node (ref "X1") (pin "VBUS") (pinfunction "VBUS_VBUS") (pintype "bidirectional"))
    )
    (net (code "84") (name "Net-(IC1-3V3OUT)") (class "Default")
      (node (ref "C13") (pin "2") (pinfunction "2_2") (pintype "passive"))
      (node (ref "IC1") (pin "17") (pinfunction "3V3OUT_17") (pintype "output"))
      (node (ref "IC1") (pin "4") (pinfunction "VCCIO_4") (pintype "power_in"))
    )
    (net (code "85") (name "Net-(IC1-USBDM)") (class "Default")
      (node (ref "IC1") (pin "16") (pinfunction "USBDM_16") (pintype "bidirectional"))
      (node (ref "X1") (pin "D-") (pinfunction "D-_D-") (pintype "bidirectional"))
    )
    (net (code "86") (name "Net-(IC1-USBDP)") (class "Default")
      (node (ref "IC1") (pin "15") (pinfunction "USBDP_15") (pintype "bidirectional"))
      (node (ref "X1") (pin "D+") (pinfunction "D+_D+") (pintype "bidirectional"))
    )
    (net (code "87") (name "Net-(IC1-VCC)") (class "Default")
      (node (ref "C11") (pin "2") (pinfunction "2_2") (pintype "passive"))
      (node (ref "C12") (pin "2") (pinfunction "2_2") (pintype "passive"))
      (node (ref "IC1") (pin "20") (pinfunction "VCC_20") (pintype "power_in"))
      (node (ref "L2") (pin "2") (pinfunction "2_2") (pintype "bidirectional"))
    )
    (net (code "88") (name "Net-(U1-IREF)") (class "Default")
      (node (ref "R3") (pin "2") (pinfunction "2_2") (pintype "passive"))
      (node (ref "U1") (pin "27") (pinfunction "IREF_27") (pintype "bidirectional"))
    )
    (net (code "89") (name "Net-(U1-SOUT)") (class "Default")
      (node (ref "U1") (pin "24") (pinfunction "SOUT_24") (pintype "bidirectional"))
      (node (ref "U2") (pin "5") (pinfunction "SIN_5") (pintype "bidirectional"))
    )
    (net (code "90") (name "Net-(U2-IREF)") (class "Default")
      (node (ref "R1") (pin "2") (pinfunction "2_2") (pintype "passive"))
      (node (ref "U2") (pin "27") (pinfunction "IREF_27") (pintype "bidirectional"))
    )
    (net (code "91") (name "Net-(U2-SOUT)") (class "Default")
      (node (ref "U2") (pin "24") (pinfunction "SOUT_24") (pintype "bidirectional"))
      (node (ref "U3") (pin "5") (pinfunction "SIN_5") (pintype "bidirectional"))
    )
    (net (code "92") (name "Net-(U3-IREF)") (class "Default")
      (node (ref "R2") (pin "2") (pinfunction "2_2") (pintype "passive"))
      (node (ref "U3") (pin "27") (pinfunction "IREF_27") (pintype "bidirectional"))
    )
    (net (code "93") (name "Net-(U7-BST)") (class "Default")
      (node (ref "C1") (pin "1") (pinfunction "1_1") (pintype "passive"))
      (node (ref "U7") (pin "1") (pinfunction "BST_1") (pintype "bidirectional"))
    )
    (net (code "94") (name "Net-(U7-EN)") (class "Default")
      (node (ref "R4") (pin "1") (pinfunction "1_1") (pintype "passive"))
      (node (ref "U7") (pin "4") (pinfunction "EN_4") (pintype "bidirectional"))
    )
    (net (code "95") (name "Net-(U7-FB)") (class "Default")
      (node (ref "R5") (pin "2") (pinfunction "2_2") (pintype "passive"))
      (node (ref "R6") (pin "1") (pinfunction "1_1") (pintype "passive"))
      (node (ref "U7") (pin "3") (pinfunction "FB_3") (pintype "bidirectional"))
    )
    (net (code "96") (name "Net-(U7-LX)") (class "Default")
      (node (ref "C1") (pin "2") (pinfunction "2_2") (pintype "passive"))
      (node (ref "D1") (pin "C") (pinfunction "C_C") (pintype "bidirectional"))
      (node (ref "L1") (pin "1") (pinfunction "1_1") (pintype "passive"))
      (node (ref "U7") (pin "6") (pinfunction "LX_6") (pintype "bidirectional"))
    )
    (net (code "97") (name "VCC") (class "Default")
      (node (ref "C14") (pin "2") (pinfunction "2_2") (pintype "passive"))
      (node (ref "C15") (pin "2") (pinfunction "2_2") (pintype "passive"))
      (node (ref "C16") (pin "2") (pinfunction "2_2") (pintype "passive"))
      (node (ref "C17") (pin "2") (pinfunction "2_2") (pintype "passive"))
      (node (ref "C18") (pin "2") (pinfunction "2_2") (pintype "passive"))
      (node (ref "C19") (pin "1") (pinfunction "1_1") (pintype "passive"))
      (node (ref "C2") (pin "2") (pinfunction "2_2") (pintype "passive"))
      (node (ref "C3") (pin "2") (pinfunction "2_2") (pintype "passive"))
      (node (ref "C6") (pin "2") (pinfunction "2_2") (pintype "passive"))
      (node (ref "C7") (pin "2") (pinfunction "2_2") (pintype "passive"))
      (node (ref "C8") (pin "2") (pinfunction "2_2") (pintype "passive"))
      (node (ref "C9") (pin "2") (pinfunction "2_2") (pintype "passive"))
      (node (ref "JP2") (pin "4") (pinfunction "4_4") (pintype "passive"))
      (node (ref "JP7") (pin "9") (pinfunction "9_9") (pintype "passive"))
      (node (ref "L1") (pin "2") (pinfunction "2_2") (pintype "passive"))
      (node (ref "R10") (pin "1") (pinfunction "1_1") (pintype "passive"))
      (node (ref "R5") (pin "1") (pinfunction "1_1") (pintype "passive"))
      (node (ref "R7") (pin "1") (pinfunction "1_1") (pintype "passive"))
      (node (ref "R8") (pin "1") (pinfunction "1_1") (pintype "passive"))
      (node (ref "U1") (pin "28") (pinfunction "VCC_28") (pintype "bidirectional"))
      (node (ref "U2") (pin "28") (pinfunction "VCC_28") (pintype "bidirectional"))
      (node (ref "U3") (pin "28") (pinfunction "VCC_28") (pintype "bidirectional"))
      (node (ref "U4") (pin "20") (pinfunction "VCC_20") (pintype "bidirectional"))
      (node (ref "U5") (pin "17") (pinfunction "VCC_17") (pintype "power_in"))
      (node (ref "U5") (pin "27") (pinfunction "AVCC_27") (pintype "power_in"))
      (node (ref "U5") (pin "29") (pinfunction "AREF_29") (pintype "power_in"))
      (node (ref "U5") (pin "38") (pinfunction "VCC_38") (pintype "power_in"))
      (node (ref "U5") (pin "5") (pinfunction "VCC_5") (pintype "power_in"))
      (node (ref "U6") (pin "10") (pinfunction "3V3D_10") (pintype "bidirectional"))
      (node (ref "U6") (pin "11") (pinfunction "3V3D_11") (pintype "bidirectional"))
      (node (ref "U8") (pin "5") (pinfunction "VCC_5") (pintype "power_in"))
    )
    (net (code "98") (name "VIN") (class "Default")
      (node (ref "C20") (pin "+") (pinfunction "+_+") (pintype "passive"))
      (node (ref "C21") (pin "2") (pinfunction "2_2") (pintype "passive"))
      (node (ref "C22") (pin "2") (pinfunction "2_2") (pintype "passive"))
      (node (ref "C23") (pin "2") (pinfunction "2_2") (pintype "passive"))
      (node (ref "C24") (pin "2") (pinfunction "2_2") (pintype "passive"))
      (node (ref "C4") (pin "2") (pinfunction "2_2") (pintype "passive"))
      (node (ref "C5") (pin "2") (pinfunction "2_2") (pintype "passive"))
      (node (ref "JP1") (pin "1") (pinfunction "1_1") (pintype "passive"))
      (node (ref "JP10") (pin "1") (pinfunction "1_1") (pintype "passive"))
      (node (ref "JP10") (pin "11") (pinfunction "11_11") (pintype "passive"))
      (node (ref "JP10") (pin "3") (pinfunction "3_3") (pintype "passive"))
      (node (ref "JP10") (pin "5") (pinfunction "5_5") (pintype "passive"))
      (node (ref "JP10") (pin "7") (pinfunction "7_7") (pintype "passive"))
      (node (ref "JP10") (pin "9") (pinfunction "9_9") (pintype "passive"))
      (node (ref "JP3") (pin "1") (pinfunction "1_1") (pintype "passive"))
      (node (ref "JP3") (pin "13") (pinfunction "13_13") (pintype "passive"))
      (node (ref "JP3") (pin "5") (pinfunction "5_5") (pintype "passive"))
      (node (ref "JP3") (pin "9") (pinfunction "9_9") (pintype "passive"))
      (node (ref "JP4") (pin "1") (pinfunction "1_1") (pintype "passive"))
      (node (ref "JP4") (pin "13") (pinfunction "13_13") (pintype "passive"))
      (node (ref "JP4") (pin "5") (pinfunction "5_5") (pintype "passive"))
      (node (ref "JP4") (pin "9") (pinfunction "9_9") (pintype "passive"))
      (node (ref "JP5") (pin "1") (pinfunction "1_1") (pintype "passive"))
      (node (ref "JP5") (pin "13") (pinfunction "13_13") (pintype "passive"))
      (node (ref "JP5") (pin "5") (pinfunction "5_5") (pintype "passive"))
      (node (ref "JP5") (pin "9") (pinfunction "9_9") (pintype "passive"))
      (node (ref "JP6") (pin "1") (pinfunction "1_1") (pintype "passive"))
      (node (ref "JP6") (pin "13") (pinfunction "13_13") (pintype "passive"))
      (node (ref "JP6") (pin "5") (pinfunction "5_5") (pintype "passive"))
      (node (ref "JP6") (pin "9") (pinfunction "9_9") (pintype "passive"))
      (node (ref "JP9") (pin "10") (pinfunction "10_10") (pintype "passive"))
      (node (ref "JP9") (pin "12") (pinfunction "12_12") (pintype "passive"))
      (node (ref "JP9") (pin "2") (pinfunction "2_2") (pintype "passive"))
      (node (ref "JP9") (pin "4") (pinfunction "4_4") (pintype "passive"))
      (node (ref "JP9") (pin "6") (pinfunction "6_6") (pintype "passive"))
      (node (ref "JP9") (pin "8") (pinfunction "8_8") (pintype "passive"))
      (node (ref "R4") (pin "2") (pinfunction "2_2") (pintype "passive"))
      (node (ref "U7") (pin "5") (pinfunction "VIN_5") (pintype "bidirectional"))
    )
    (net (code "99") (name "unconnected-(IC1-CTS-Pad11)") (class "Default")
      (node (ref "IC1") (pin "11") (pinfunction "CTS_11") (pintype "input"))
    )
    (net (code "100") (name "unconnected-(IC1-DCD-Pad10)") (class "Default")
      (node (ref "IC1") (pin "10") (pinfunction "DCD_10") (pintype "input"))
    )
    (net (code "101") (name "unconnected-(IC1-DSR-Pad9)") (class "Default")
      (node (ref "IC1") (pin "9") (pinfunction "DSR_9") (pintype "input"))
    )
    (net (code "102") (name "unconnected-(IC1-DTR-Pad2)") (class "Default")
      (node (ref "IC1") (pin "2") (pinfunction "DTR_2") (pintype "output"))
    )
    (net (code "103") (name "unconnected-(IC1-OSCI-Pad27)") (class "Default")
      (node (ref "IC1") (pin "27") (pinfunction "OSCI_27") (pintype "input"))
    )
    (net (code "104") (name "unconnected-(IC1-OSCO-Pad28)") (class "Default")
      (node (ref "IC1") (pin "28") (pinfunction "OSCO_28") (pintype "output"))
    )
    (net (code "105") (name "unconnected-(IC1-PWREN-Pad14)") (class "Default")
      (node (ref "IC1") (pin "14") (pinfunction "PWREN_14") (pintype "input"))
    )
    (net (code "106") (name "unconnected-(IC1-RESET-Pad19)") (class "Default")
      (node (ref "IC1") (pin "19") (pinfunction "RESET_19") (pintype "input"))
    )
    (net (code "107") (name "unconnected-(IC1-RI-Pad6)") (class "Default")
      (node (ref "IC1") (pin "6") (pinfunction "RI_6") (pintype "input"))
    )
    (net (code "108") (name "unconnected-(IC1-RTS-Pad3)") (class "Default")
      (node (ref "IC1") (pin "3") (pinfunction "RTS_3") (pintype "output"))
    )
    (net (code "109") (name "unconnected-(IC1-RXLED-Pad22)") (class "Default")
      (node (ref "IC1") (pin "22") (pinfunction "RXLED_22") (pintype "input"))
    )
    (net (code "110") (name "unconnected-(IC1-SLEEP-Pad12)") (class "Default")
      (node (ref "IC1") (pin "12") (pinfunction "SLEEP_12") (pintype "input"))
    )
    (net (code "111") (name "unconnected-(IC1-TXDEN-Pad13)") (class "Default")
      (node (ref "IC1") (pin "13") (pinfunction "TXDEN_13") (pintype "input"))
    )
    (net (code "112") (name "unconnected-(IC1-TXLED-Pad23)") (class "Default")
      (node (ref "IC1") (pin "23") (pinfunction "TXLED_23") (pintype "input"))
    )
    (net (code "113") (name "unconnected-(JP2-Pad7)") (class "Default")
      (node (ref "JP2") (pin "7") (pinfunction "7_7") (pintype "passive"))
    )
    (net (code "114") (name "unconnected-(JP2-Pad8)") (class "Default")
      (node (ref "JP2") (pin "8") (pinfunction "8_8") (pintype "passive"))
    )
    (net (code "115") (name "unconnected-(JP15-Pad1)") (class "Default")
      (node (ref "JP15") (pin "1") (pinfunction "1_1") (pintype "passive"))
    )
    (net (code "116") (name "unconnected-(JP15-Pad2)") (class "Default")
      (node (ref "JP15") (pin "2") (pinfunction "2_2") (pintype "passive"))
    )
    (net (code "117") (name "unconnected-(JP15-Pad15)") (class "Default")
      (node (ref "JP15") (pin "15") (pinfunction "15_15") (pintype "passive"))
    )
    (net (code "118") (name "unconnected-(JP15-Pad16)") (class "Default")
      (node (ref "JP15") (pin "16") (pinfunction "16_16") (pintype "passive"))
    )
    (net (code "119") (name "unconnected-(U5-(ADC6{slash}PCINT6)PA6-Pad31)") (class "Default")
      (node (ref "U5") (pin "31") (pinfunction "(ADC6/PCINT6)PA6_31") (pintype "bidirectional"))
    )
    (net (code "120") (name "unconnected-(U5-(ADC7{slash}PCINT7)PA7-Pad30)") (class "Default")
      (node (ref "U5") (pin "30") (pinfunction "(ADC7/PCINT7)PA7_30") (pintype "bidirectional"))
    )
    (net (code "121") (name "unconnected-(U5-(SCL{slash}PCINT16)PC0-Pad19)") (class "Default")
      (node (ref "U5") (pin "19") (pinfunction "(SCL/PCINT16)PC0_19") (pintype "bidirectional"))
    )
    (net (code "122") (name "unconnected-(U5-(SDA{slash}PCINT17)PC1-Pad20)") (class "Default")
      (node (ref "U5") (pin "20") (pinfunction "(SDA/PCINT17)PC1_20") (pintype "bidirectional"))
    )
    (net (code "123") (name "unconnected-(U5-(TOSC1{slash}PCINT22)PC6-Pad25)") (class "Default")
      (node (ref "U5") (pin "25") (pinfunction "(TOSC1/PCINT22)PC6_25") (pintype "bidirectional"))
    )
    (net (code "124") (name "unconnected-(U5-(TOSC2{slash}PCINT23)PC7-Pad26)") (class "Default")
      (node (ref "U5") (pin "26") (pinfunction "(TOSC2/PCINT23)PC7_26") (pintype "bidirectional"))
    )
    (net (code "125") (name "unconnected-(U5-PB1(PCINT9{slash}CLKO{slash}T1)-Pad41)") (class "Default")
      (node (ref "U5") (pin "41") (pinfunction "PB1(PCINT9/CLKO/T1)_41") (pintype "bidirectional"))
    )
    (net (code "126") (name "unconnected-(U5-PB3(PCINT11{slash}OC0A{slash}AIN1)-Pad43)") (class "Default")
      (node (ref "U5") (pin "43") (pinfunction "PB3(PCINT11/OC0A/AIN1)_43") (pintype "bidirectional"))
    )
    (net (code "127") (name "unconnected-(U5-PB4(PCINT12{slash}OC0B{slash}SS)-Pad44)") (class "Default")
      (node (ref "U5") (pin "44") (pinfunction "PB4(PCINT12/OC0B/SS)_44") (pintype "bidirectional"))
    )
    (net (code "128") (name "unconnected-(U5-PD7(OC2A{slash}PCINT31)-Pad16)") (class "Default")
      (node (ref "U5") (pin "16") (pinfunction "PD7(OC2A/PCINT31)_16") (pintype "bidirectional"))
    )
    (net (code "129") (name "unconnected-(U5-XTAL1-Pad8)") (class "Default")
      (node (ref "U5") (pin "8") (pinfunction "XTAL1_8") (pintype "output"))
    )
    (net (code "130") (name "unconnected-(U5-XTAL2-Pad7)") (class "Default")
      (node (ref "U5") (pin "7") (pinfunction "XTAL2_7") (pintype "output"))
    )
  )
)
